# NRF.net
KiCad netlist of a schematic drawn in Altium Designer
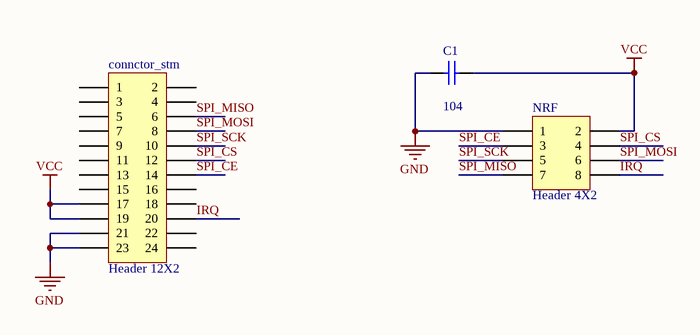
[diagram p0: NRF.SchDoc]

(export (version "E")
  (design (tool "Eeschema 10.0.6"))
  (components
    (comp (ref "C1")
      (value "104")
      (footprint "C1206")
      (description "Capacitor (Semiconductor SIM Model)")
      (fields (field (name "PUBLISHER") "Altium Limited"))
      (libsource (lib "Miscellaneous Devices") (part "Cap Semi"))
    )
    (comp (ref "connctor_stm")
      (value "Header 12X2")
      (footprint "HDR2X12")
      (description "Header, 12-Pin, Dual row")
      (fields (field (name "PUBLISHER") "Altium Limited"))
      (libsource (lib "Miscellaneous Connectors") (part "Header 12X2"))
    )
    (comp (ref "NRF")
      (value "Header 4X2")
      (footprint "HDR2X4")
      (description "Header, 4-Pin, Dual row")
      (fields (field (name "PUBLISHER") "Altium Limited"))
      (libsource (lib "Miscellaneous Connectors") (part "Header 4X2"))
    )
  )
  (nets
    (net (code "1") (name "/IRQ") (class "Default")
      (node (ref "NRF") (pin "8") (pinfunction "8_8") (pintype "passive"))
      (node (ref "connctor_stm") (pin "20") (pinfunction "20_20") (pintype "passive"))
    )
    (net (code "2") (name "/SPI_CE") (class "Default")
      (node (ref "NRF") (pin "3") (pinfunction "3_3") (pintype "passive"))
      (node (ref "connctor_stm") (pin "14") (pinfunction "14_14") (pintype "passive"))
    )
    (net (code "3") (name "/SPI_CS") (class "Default")
      (node (ref "NRF") (pin "4") (pinfunction "4_4") (pintype "passive"))
      (node (ref "connctor_stm") (pin "12") (pinfunction "12_12") (pintype "passive"))
    )
    (net (code "4") (name "/SPI_MISO") (class "Default")
      (node (ref "NRF") (pin "7") (pinfunction "7_7") (pintype "passive"))
      (node (ref "connctor_stm") (pin "6") (pinfunction "6_6") (pintype "passive"))
    )
    (net (code "5") (name "/SPI_MOSI") (class "Default")
      (node (ref "NRF") (pin "6") (pinfunction "6_6") (pintype "passive"))
      (node (ref "connctor_stm") (pin "8") (pinfunction "8_8") (pintype "passive"))
    )
    (net (code "6") (name "/SPI_SCK") (class "Default")
      (node (ref "NRF") (pin "5") (pinfunction "5_5") (pintype "passive"))
      (node (ref "connctor_stm") (pin "10") (pinfunction "10_10") (pintype "passive"))
    )
    (net (code "7") (name "GND") (class "Default")
      (node (ref "C1") (pin "1") (pinfunction "1_1") (pintype "passive"))
      (node (ref "NRF") (pin "1") (pinfunction "1_1") (pintype "passive"))
      (node (ref "connctor_stm") (pin "21") (pinfunction "21_21") (pintype "passive"))
      (node (ref "connctor_stm") (pin "23") (pinfunction "23_23") (pintype "passive"))
    )
    (net (code "8") (name "VCC") (class "Default")
      (node (ref "C1") (pin "2") (pinfunction "2_2") (pintype "passive"))
      (node (ref "NRF") (pin "2") (pinfunction "2_2") (pintype "passive"))
      (node (ref "connctor_stm") (pin "17") (pinfunction "17_17") (pintype "passive"))
      (node (ref "connctor_stm") (pin "19") (pinfunction "19_19") (pintype "passive"))
    )
    (net (code "9") (name "unconnected-(connctor_stm-Pad1)") (class "Default")
      (node (ref "connctor_stm") (pin "1") (pinfunction "1_1") (pintype "passive"))
    )
    (net (code "10") (name "unconnected-(connctor_stm-Pad2)") (class "Default")
      (node (ref "connctor_stm") (pin "2") (pinfunction "2_2") (pintype "passive"))
    )
    (net (code "11") (name "unconnected-(connctor_stm-Pad3)") (class "Default")
      (node (ref "connctor_stm") (pin "3") (pinfunction "3_3") (pintype "passive"))
    )
    (net (code "12") (name "unconnected-(connctor_stm-Pad4)") (class "Default")
      (node (ref "connctor_stm") (pin "4") (pinfunction "4_4") (pintype "passive"))
    )
    (net (code "13") (name "unconnected-(connctor_stm-Pad5)") (class "Default")
      (node (ref "connctor_stm") (pin "5") (pinfunction "5_5") (pintype "passive"))
    )
    (net (code "14") (name "unconnected-(connctor_stm-Pad7)") (class "Default")
      (node (ref "connctor_stm") (pin "7") (pinfunction "7_7") (pintype "passive"))
    )
    (net (code "15") (name "unconnected-(connctor_stm-Pad9)") (class "Default")
      (node (ref "connctor_stm") (pin "9") (pinfunction "9_9") (pintype "passive"))
    )
    (net (code "16") (name "unconnected-(connctor_stm-Pad11)") (class "Default")
      (node (ref "connctor_stm") (pin "11") (pinfunction "11_11") (pintype "passive"))
    )
    (net (code "17") (name "unconnected-(connctor_stm-Pad13)") (class "Default")
      (node (ref "connctor_stm") (pin "13") (pinfunction "13_13") (pintype "passive"))
    )
    (net (code "18") (name "unconnected-(connctor_stm-Pad15)") (class "Default")
      (node (ref "connctor_stm") (pin "15") (pinfunction "15_15") (pintype "passive"))
    )
    (net (code "19") (name "unconnected-(connctor_stm-Pad16)") (class "Default")
      (node (ref "connctor_stm") (pin "16") (pinfunction "16_16") (pintype "passive"))
    )
    (net (code "20") (name "unconnected-(connctor_stm-Pad18)") (class "Default")
      (node (ref "connctor_stm") (pin "18") (pinfunction "18_18") (pintype "passive"))
    )
    (net (code "21") (name "unconnected-(connctor_stm-Pad22)") (class "Default")
      (node (ref "connctor_stm") (pin "22") (pinfunction "22_22") (pintype "passive"))
    )
    (net (code "22") (name "unconnected-(connctor_stm-Pad24)") (class "Default")
      (node (ref "connctor_stm") (pin "24") (pinfunction "24_24") (pintype "passive"))
    )
  )
)
